# 0-HygroSensor.net
KiCad netlist of a schematic drawn in Altium Designer
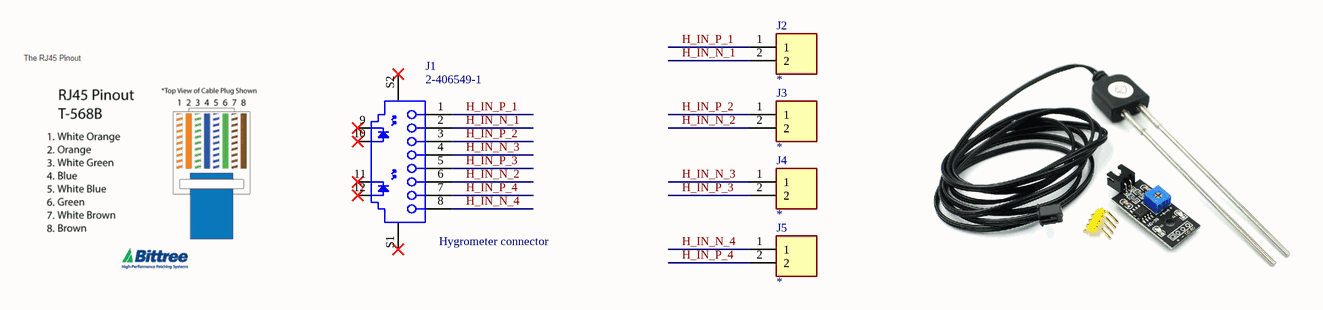
[diagram p0: 0-HygroSensor.SchDoc]

(export (version "E")
  (design (tool "Eeschema 10.0.6"))
  (components
    (comp (ref "J1")
      (value "2-406549-1")
      (footprint "TECO-2-406549-1_V")
      (description "RJ45 Connector, Pitch 1.016 mm, 8 Position, Height 14.22 mm, Tail Length 3.18 mm, RoHS, Tray")
      (fields (field (name "MANUFACTURER") "TE Connectivity"))
      (libsource (lib "Altium Content Vault") (part "RJ45-12-2SHLD_A"))
    )
    (comp (ref "J2")
      (value "282841-2")
      (footprint "TE_282841-2")
      (description "Conn Terminal Block 2 POS 5.08mm Solder ST Thru-Hole 17.5A/Contact")
      (fields (field (name "MF") "TE Connectivity") (field (name "COMMENT_1") "*"))
      (libsource (lib "PTR500-2") (part "282841-2"))
    )
    (comp (ref "J3")
      (value "282841-2")
      (footprint "TE_282841-2")
      (description "Conn Terminal Block 2 POS 5.08mm Solder ST Thru-Hole 17.5A/Contact")
      (fields (field (name "MF") "TE Connectivity") (field (name "COMMENT_1") "*"))
      (libsource (lib "PTR500-2") (part "282841-2"))
    )
    (comp (ref "J4")
      (value "282841-2")
      (footprint "TE_282841-2")
      (description "Conn Terminal Block 2 POS 5.08mm Solder ST Thru-Hole 17.5A/Contact")
      (fields (field (name "MF") "TE Connectivity") (field (name "COMMENT_1") "*"))
      (libsource (lib "PTR500-2") (part "282841-2"))
    )
    (comp (ref "J5")
      (value "282841-2")
      (footprint "TE_282841-2")
      (description "Conn Terminal Block 2 POS 5.08mm Solder ST Thru-Hole 17.5A/Contact")
      (fields (field (name "MF") "TE Connectivity") (field (name "COMMENT_1") "*"))
      (libsource (lib "PTR500-2") (part "282841-2"))
    )
  )
  (nets
    (net (code "1") (name "/H_IN_N_1") (class "Default")
      (node (ref "J1") (pin "2") (pinfunction "2_2") (pintype "passive"))
      (node (ref "J2") (pin "2") (pinfunction "2_2") (pintype "passive"))
    )
    (net (code "2") (name "/H_IN_N_2") (class "Default")
      (node (ref "J1") (pin "6") (pinfunction "6_6") (pintype "passive"))
      (node (ref "J3") (pin "2") (pinfunction "2_2") (pintype "passive"))
    )
    (net (code "3") (name "/H_IN_N_3") (class "Default")
      (node (ref "J1") (pin "4") (pinfunction "4_4") (pintype "passive"))
      (node (ref "J4") (pin "1") (pinfunction "1_1") (pintype "passive"))
    )
    (net (code "4") (name "/H_IN_N_4") (class "Default")
      (node (ref "J1") (pin "8") (pinfunction "8_8") (pintype "passive"))
      (node (ref "J5") (pin "1") (pinfunction "1_1") (pintype "passive"))
    )
    (net (code "5") (name "/H_IN_P_1") (class "Default")
      (node (ref "J1") (pin "1") (pinfunction "1_1") (pintype "passive"))
      (node (ref "J2") (pin "1") (pinfunction "1_1") (pintype "passive"))
    )
    (net (code "6") (name "/H_IN_P_2") (class "Default")
      (node (ref "J1") (pin "3") (pinfunction "3_3") (pintype "passive"))
      (node (ref "J3") (pin "1") (pinfunction "1_1") (pintype "passive"))
    )
    (net (code "7") (name "/H_IN_P_3") (class "Default")
      (node (ref "J1") (pin "5") (pinfunction "5_5") (pintype "passive"))
      (node (ref "J4") (pin "2") (pinfunction "2_2") (pintype "passive"))
    )
    (net (code "8") (name "/H_IN_P_4") (class "Default")
      (node (ref "J1") (pin "7") (pinfunction "7_7") (pintype "passive"))
      (node (ref "J5") (pin "2") (pinfunction "2_2") (pintype "passive"))
    )
    (net (code "9") (name "unconnected-(J1-Pad9)") (class "Default")
      (node (ref "J1") (pin "9") (pinfunction "9_9") (pintype "passive+no_connect"))
    )
    (net (code "10") (name "unconnected-(J1-Pad10)") (class "Default")
      (node (ref "J1") (pin "10") (pinfunction "10_10") (pintype "passive+no_connect"))
    )
    (net (code "11") (name "unconnected-(J1-Pad11)") (class "Default")
      (node (ref "J1") (pin "11") (pinfunction "11_11") (pintype "passive+no_connect"))
    )
    (net (code "12") (name "unconnected-(J1-Pad12)") (class "Default")
      (node (ref "J1") (pin "12") (pinfunction "12_12") (pintype "passive+no_connect"))
    )
    (net (code "13") (name "unconnected-(J1-PadS1)") (class "Default")
      (node (ref "J1") (pin "S1") (pinfunction "S1_S1") (pintype "passive+no_connect"))
    )
    (net (code "14") (name "unconnected-(J1-PadS2)") (class "Default")
      (node (ref "J1") (pin "S2") (pinfunction "S2_S2") (pintype "passive+no_connect"))
    )
  )
)
